# 4_POWER_48_TO_12.net
KiCad netlist of a schematic drawn in Altium Designer
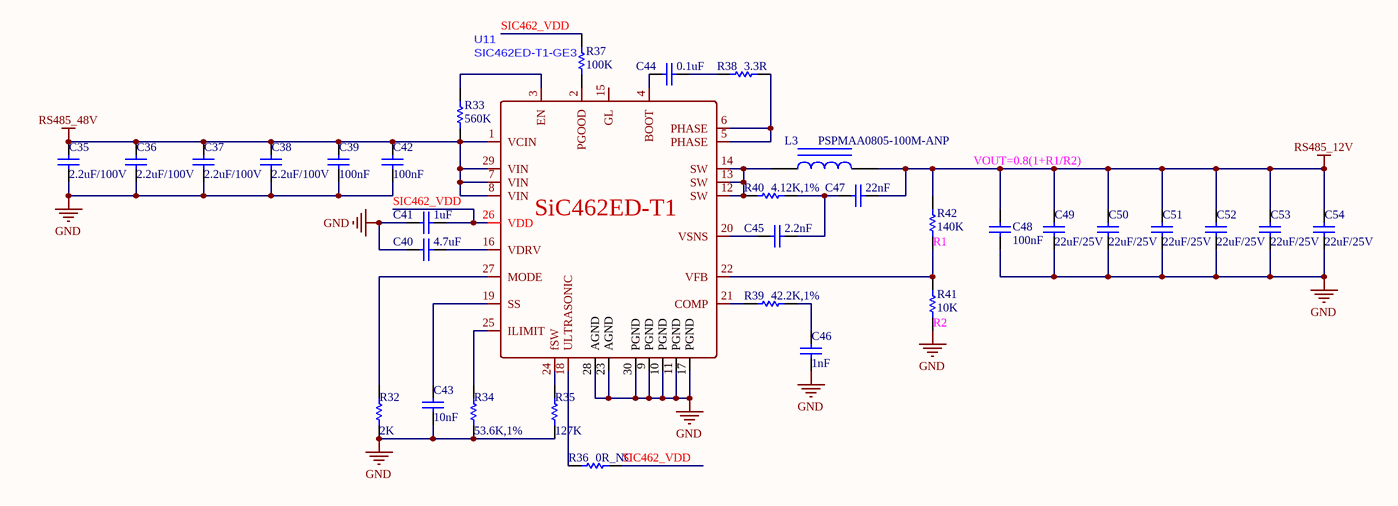
[diagram p0: 4.POWER_48_TO_12.SchDoc]

(export (version "E")
  (design (tool "Eeschema 10.0.6"))
  (components
    (comp (ref "C35")
      (value "2.2uF/100V")
      (footprint "1206C")
      (description "Capacitor")
      (fields (field (name "PARTNUMBER") "CAP100NF") (field (name "PUBLISHER") "Altium Limited"))
      (libsource (lib "Miscellaneous Devices") (part "Cap"))
    )
    (comp (ref "C36")
      (value "2.2uF/100V")
      (footprint "1206C")
      (description "Capacitor")
      (fields (field (name "PARTNUMBER") "CAP100NF") (field (name "PUBLISHER") "Altium Limited"))
      (libsource (lib "Miscellaneous Devices") (part "Cap"))
    )
    (comp (ref "C37")
      (value "2.2uF/100V")
      (footprint "1206C")
      (description "Capacitor")
      (fields (field (name "PARTNUMBER") "CAP100NF") (field (name "PUBLISHER") "Altium Limited"))
      (libsource (lib "Miscellaneous Devices") (part "Cap"))
    )
    (comp (ref "C38")
      (value "2.2uF/100V")
      (footprint "1206C")
      (description "Capacitor")
      (fields (field (name "PARTNUMBER") "CAP100NF") (field (name "PUBLISHER") "Altium Limited"))
      (libsource (lib "Miscellaneous Devices") (part "Cap"))
    )
    (comp (ref "C39")
      (value "100nF")
      (footprint "0402")
      (description "Capacitor")
      (fields (field (name "PARTNUMBER") "CAP100NF") (field (name "PUBLISHER") "Altium Limited"))
      (libsource (lib "Miscellaneous Devices") (part "Cap"))
    )
    (comp (ref "C40")
      (value "4.7uF")
      (footprint "0402")
      (description "Capacitor")
      (fields (field (name "PARTNUMBER") "CAP100NF") (field (name "PUBLISHER") "Altium Limited"))
      (libsource (lib "Miscellaneous Devices") (part "Cap"))
    )
    (comp (ref "C41")
      (value "1uF")
      (footprint "0402")
      (description "Capacitor")
      (fields (field (name "PARTNUMBER") "CAP100NF") (field (name "PUBLISHER") "Altium Limited"))
      (libsource (lib "Miscellaneous Devices") (part "Cap"))
    )
    (comp (ref "C42")
      (value "100nF")
      (footprint "0402")
      (description "Capacitor")
      (fields (field (name "PARTNUMBER") "CAP100NF") (field (name "PUBLISHER") "Altium Limited"))
      (libsource (lib "Miscellaneous Devices") (part "Cap"))
    )
    (comp (ref "C43")
      (value "10nF")
      (footprint "0402")
      (description "Capacitor")
      (fields (field (name "PARTNUMBER") "CAP100NF") (field (name "PUBLISHER") "Altium Limited"))
      (libsource (lib "Miscellaneous Devices") (part "Cap"))
    )
    (comp (ref "C44")
      (value "0.1uF")
      (footprint "0402")
      (description "Capacitor")
      (fields (field (name "PARTNUMBER") "CAP100NF") (field (name "PUBLISHER") "Altium Limited"))
      (libsource (lib "Miscellaneous Devices") (part "Cap"))
    )
    (comp (ref "C45")
      (value "2.2nF")
      (footprint "0402")
      (description "Capacitor")
      (fields (field (name "PARTNUMBER") "CAP100NF") (field (name "PUBLISHER") "Altium Limited"))
      (libsource (lib "Miscellaneous Devices") (part "Cap"))
    )
    (comp (ref "C46")
      (value "1nF")
      (footprint "0402")
      (description "Capacitor")
      (fields (field (name "PARTNUMBER") "CAP100NF") (field (name "PUBLISHER") "Altium Limited"))
      (libsource (lib "Miscellaneous Devices") (part "Cap"))
    )
    (comp (ref "C47")
      (value "22nF")
      (footprint "0402")
      (description "Capacitor")
      (fields (field (name "PARTNUMBER") "CAP100NF") (field (name "PUBLISHER") "Altium Limited"))
      (libsource (lib "Miscellaneous Devices") (part "Cap"))
    )
    (comp (ref "C48")
      (value "100nF")
      (footprint "0402")
      (description "Capacitor")
      (fields (field (name "PARTNUMBER") "CAP100NF") (field (name "PUBLISHER") "Altium Limited"))
      (libsource (lib "Miscellaneous Devices") (part "Cap"))
    )
    (comp (ref "C49")
      (value "22uF/25V")
      (footprint "0805C")
      (description "Capacitor")
      (fields (field (name "PARTNUMBER") "CAP100NF") (field (name "PUBLISHER") "Altium Limited"))
      (libsource (lib "Miscellaneous Devices") (part "Cap"))
    )
    (comp (ref "C50")
      (value "22uF/25V")
      (footprint "0805C")
      (description "Capacitor")
      (fields (field (name "PARTNUMBER") "CAP100NF") (field (name "PUBLISHER") "Altium Limited"))
      (libsource (lib "Miscellaneous Devices") (part "Cap"))
    )
    (comp (ref "C51")
      (value "22uF/25V")
      (footprint "0805C")
      (description "Capacitor")
      (fields (field (name "PARTNUMBER") "CAP100NF") (field (name "PUBLISHER") "Altium Limited"))
      (libsource (lib "Miscellaneous Devices") (part "Cap"))
    )
    (comp (ref "C52")
      (value "22uF/25V")
      (footprint "0805C")
      (description "Capacitor")
      (fields (field (name "PARTNUMBER") "CAP100NF") (field (name "PUBLISHER") "Altium Limited"))
      (libsource (lib "Miscellaneous Devices") (part "Cap"))
    )
    (comp (ref "C53")
      (value "22uF/25V")
      (footprint "0805C")
      (description "Capacitor")
      (fields (field (name "PARTNUMBER") "CAP100NF") (field (name "PUBLISHER") "Altium Limited"))
      (libsource (lib "Miscellaneous Devices") (part "Cap"))
    )
    (comp (ref "C54")
      (value "22uF/25V")
      (footprint "0805C")
      (description "Capacitor")
      (fields (field (name "PARTNUMBER") "CAP100NF") (field (name "PUBLISHER") "Altium Limited"))
      (libsource (lib "Miscellaneous Devices") (part "Cap"))
    )
    (comp (ref "L3")
      (value "PSPMAA0805-100M-ANP")
      (footprint "IND-SMD_L8.5-W8.0_PCC-M0854M")
      (description "贴片电感")
      (libsource (lib "Miscellaneous Devices LC") (part "0603 3.9nH 0.3nH"))
    )
    (comp (ref "R32")
      (value "2K")
      (footprint "0402")
      (description "Resistor")
      (fields (field (name "PARTNUMBER") "RES22R") (field (name "PUBLISHER") "Altium Limited"))
      (libsource (lib "Miscellaneous Devices") (part "Res1"))
    )
    (comp (ref "R33")
      (value "560K")
      (footprint "0402")
      (description "Resistor")
      (fields (field (name "PARTNUMBER") "RES22R") (field (name "PUBLISHER") "Altium Limited"))
      (libsource (lib "Miscellaneous Devices") (part "Res1"))
    )
    (comp (ref "R34")
      (value "53.6K,1%")
      (footprint "0402")
      (description "Resistor")
      (fields (field (name "PARTNUMBER") "RES22R") (field (name "PUBLISHER") "Altium Limited"))
      (libsource (lib "Miscellaneous Devices") (part "Res1"))
    )
    (comp (ref "R35")
      (value "127K")
      (footprint "0402")
      (description "Resistor")
      (fields (field (name "PARTNUMBER") "RES22R") (field (name "PUBLISHER") "Altium Limited"))
      (libsource (lib "Miscellaneous Devices") (part "Res1"))
    )
    (comp (ref "R36")
      (value "0R_NC")
      (footprint "0402")
      (description "Resistor")
      (fields (field (name "PARTNUMBER") "RES22R") (field (name "PUBLISHER") "Altium Limited"))
      (libsource (lib "Miscellaneous Devices") (part "Res1"))
    )
    (comp (ref "R37")
      (value "100K")
      (footprint "0402")
      (description "Resistor")
      (fields (field (name "PARTNUMBER") "RES22R") (field (name "PUBLISHER") "Altium Limited"))
      (libsource (lib "Miscellaneous Devices") (part "Res1"))
    )
    (comp (ref "R38")
      (value "3.3R")
      (footprint "0402")
      (description "Resistor")
      (fields (field (name "PARTNUMBER") "RES22R") (field (name "PUBLISHER") "Altium Limited"))
      (libsource (lib "Miscellaneous Devices") (part "Res1"))
    )
    (comp (ref "R39")
      (value "42.2K,1%")
      (footprint "0402")
      (description "Resistor")
      (fields (field (name "PARTNUMBER") "RES22R") (field (name "PUBLISHER") "Altium Limited"))
      (libsource (lib "Miscellaneous Devices") (part "Res1"))
    )
    (comp (ref "R40")
      (value "4.12K,1%")
      (footprint "0402")
      (description "Resistor")
      (fields (field (name "PARTNUMBER") "RES22R") (field (name "PUBLISHER") "Altium Limited"))
      (libsource (lib "Miscellaneous Devices") (part "Res1"))
    )
    (comp (ref "R41")
      (value "10K")
      (footprint "0402")
      (description "Resistor")
      (fields (field (name "PARTNUMBER") "RES22R") (field (name "PUBLISHER") "Altium Limited"))
      (libsource (lib "Miscellaneous Devices") (part "Res1"))
    )
    (comp (ref "R42")
      (value "140K")
      (footprint "0402")
      (description "Resistor")
      (fields (field (name "PARTNUMBER") "RES22R") (field (name "PUBLISHER") "Altium Limited"))
      (libsource (lib "Miscellaneous Devices") (part "Res1"))
    )
    (comp (ref "U11")
      (value "SIC462ED-T1-GE3")
      (footprint "MLP55-27_L5.0-W5.0-P0.50-TL_SIC46XXX")
      (libsource (lib "HM2") (part "SIC462ED-T1-GE3"))
    )
  )
  (nets
    (net (code "1") (name "/SIC462_VDD") (class "Default")
      (node (ref "C41") (pin "1") (pinfunction "1_1") (pintype "passive"))
      (node (ref "R36") (pin "1") (pinfunction "1_1") (pintype "passive"))
      (node (ref "R37") (pin "2") (pinfunction "2_2") (pintype "passive"))
      (node (ref "U11") (pin "26") (pinfunction "VDD_26") (pintype "passive"))
    )
    (net (code "2") (name "GND") (class "Default")
      (node (ref "C35") (pin "2") (pinfunction "2_2") (pintype "passive"))
      (node (ref "C36") (pin "2") (pinfunction "2_2") (pintype "passive"))
      (node (ref "C37") (pin "2") (pinfunction "2_2") (pintype "passive"))
      (node (ref "C38") (pin "2") (pinfunction "2_2") (pintype "passive"))
      (node (ref "C39") (pin "2") (pinfunction "2_2") (pintype "passive"))
      (node (ref "C40") (pin "2") (pinfunction "2_2") (pintype "passive"))
      (node (ref "C41") (pin "2") (pinfunction "2_2") (pintype "passive"))
      (node (ref "C42") (pin "2") (pinfunction "2_2") (pintype "passive"))
      (node (ref "C43") (pin "1") (pinfunction "1_1") (pintype "passive"))
      (node (ref "C46") (pin "1") (pinfunction "1_1") (pintype "passive"))
      (node (ref "C48") (pin "2") (pinfunction "2_2") (pintype "passive"))
      (node (ref "C49") (pin "2") (pinfunction "2_2") (pintype "passive"))
      (node (ref "C50") (pin "2") (pinfunction "2_2") (pintype "passive"))
      (node (ref "C51") (pin "2") (pinfunction "2_2") (pintype "passive"))
      (node (ref "C52") (pin "2") (pinfunction "2_2") (pintype "passive"))
      (node (ref "C53") (pin "2") (pinfunction "2_2") (pintype "passive"))
      (node (ref "C54") (pin "2") (pinfunction "2_2") (pintype "passive"))
      (node (ref "R32") (pin "2") (pinfunction "2_2") (pintype "passive"))
      (node (ref "R34") (pin "2") (pinfunction "2_2") (pintype "passive"))
      (node (ref "R35") (pin "2") (pinfunction "2_2") (pintype "passive"))
      (node (ref "R41") (pin "1") (pinfunction "1_1") (pintype "passive"))
      (node (ref "U11") (pin "10") (pinfunction "PGND_10") (pintype "passive"))
      (node (ref "U11") (pin "11") (pinfunction "PGND_11") (pintype "passive"))
      (node (ref "U11") (pin "17") (pinfunction "PGND_17") (pintype "passive"))
      (node (ref "U11") (pin "23") (pinfunction "AGND_23") (pintype "passive"))
      (node (ref "U11") (pin "28") (pinfunction "AGND_28") (pintype "passive"))
      (node (ref "U11") (pin "30") (pinfunction "PGND_30") (pintype "passive"))
      (node (ref "U11") (pin "9") (pinfunction "PGND_9") (pintype "passive"))
    )
    (net (code "3") (name "Net-(C44-Pad1)") (class "Default")
      (node (ref "C44") (pin "1") (pinfunction "1_1") (pintype "passive"))
      (node (ref "R38") (pin "1") (pinfunction "1_1") (pintype "passive"))
    )
    (net (code "4") (name "Net-(C45-Pad1)") (class "Default")
      (node (ref "C45") (pin "1") (pinfunction "1_1") (pintype "passive"))
      (node (ref "C47") (pin "1") (pinfunction "1_1") (pintype "passive"))
      (node (ref "R40") (pin "2") (pinfunction "2_2") (pintype "passive"))
    )
    (net (code "5") (name "Net-(C46-Pad2)") (class "Default")
      (node (ref "C46") (pin "2") (pinfunction "2_2") (pintype "passive"))
      (node (ref "R39") (pin "2") (pinfunction "2_2") (pintype "passive"))
    )
    (net (code "6") (name "Net-(L3-Pad1)") (class "Default")
      (node (ref "L3") (pin "1") (pinfunction "1_1") (pintype "passive"))
      (node (ref "R40") (pin "1") (pinfunction "1_1") (pintype "passive"))
      (node (ref "U11") (pin "12") (pinfunction "SW_12") (pintype "passive"))
      (node (ref "U11") (pin "13") (pinfunction "SW_13") (pintype "passive"))
      (node (ref "U11") (pin "14") (pinfunction "SW_14") (pintype "passive"))
    )
    (net (code "7") (name "Net-(R38-Pad2)") (class "Default")
      (node (ref "R38") (pin "2") (pinfunction "2_2") (pintype "passive"))
      (node (ref "U11") (pin "5") (pinfunction "PHASE_5") (pintype "passive"))
      (node (ref "U11") (pin "6") (pinfunction "PHASE_6") (pintype "passive"))
    )
    (net (code "8") (name "Net-(U11-BOOT)") (class "Default")
      (node (ref "C44") (pin "2") (pinfunction "2_2") (pintype "passive"))
      (node (ref "U11") (pin "4") (pinfunction "BOOT_4") (pintype "passive"))
    )
    (net (code "9") (name "Net-(U11-COMP)") (class "Default")
      (node (ref "R39") (pin "1") (pinfunction "1_1") (pintype "passive"))
      (node (ref "U11") (pin "21") (pinfunction "COMP_21") (pintype "passive"))
    )
    (net (code "10") (name "Net-(U11-EN)") (class "Default")
      (node (ref "R33") (pin "2") (pinfunction "2_2") (pintype "passive"))
      (node (ref "U11") (pin "3") (pinfunction "EN_3") (pintype "passive"))
    )
    (net (code "11") (name "Net-(U11-ILIMIT)") (class "Default")
      (node (ref "R34") (pin "1") (pinfunction "1_1") (pintype "passive"))
      (node (ref "U11") (pin "25") (pinfunction "ILIMIT_25") (pintype "passive"))
    )
    (net (code "12") (name "Net-(U11-MODE)") (class "Default")
      (node (ref "R32") (pin "1") (pinfunction "1_1") (pintype "passive"))
      (node (ref "U11") (pin "27") (pinfunction "MODE_27") (pintype "passive"))
    )
    (net (code "13") (name "Net-(U11-PGOOD)") (class "Default")
      (node (ref "R37") (pin "1") (pinfunction "1_1") (pintype "passive"))
      (node (ref "U11") (pin "2") (pinfunction "PGOOD_2") (pintype "passive"))
    )
    (net (code "14") (name "Net-(U11-SS)") (class "Default")
      (node (ref "C43") (pin "2") (pinfunction "2_2") (pintype "passive"))
      (node (ref "U11") (pin "19") (pinfunction "SS_19") (pintype "passive"))
    )
    (net (code "15") (name "Net-(U11-ULTRASONIC)") (class "Default")
      (node (ref "R36") (pin "2") (pinfunction "2_2") (pintype "passive"))
      (node (ref "U11") (pin "18") (pinfunction "ULTRASONIC_18") (pintype "passive"))
    )
    (net (code "16") (name "Net-(U11-VDRV)") (class "Default")
      (node (ref "C40") (pin "1") (pinfunction "1_1") (pintype "passive"))
      (node (ref "U11") (pin "16") (pinfunction "VDRV_16") (pintype "passive"))
    )
    (net (code "17") (name "Net-(U11-VFB)") (class "Default")
      (node (ref "R41") (pin "2") (pinfunction "2_2") (pintype "passive"))
      (node (ref "R42") (pin "1") (pinfunction "1_1") (pintype "passive"))
      (node (ref "U11") (pin "22") (pinfunction "VFB_22") (pintype "passive"))
    )
    (net (code "18") (name "Net-(U11-VSNS)") (class "Default")
      (node (ref "C45") (pin "2") (pinfunction "2_2") (pintype "passive"))
      (node (ref "U11") (pin "20") (pinfunction "VSNS_20") (pintype "passive"))
    )
    (net (code "19") (name "Net-(U11-fSW)") (class "Default")
      (node (ref "R35") (pin "1") (pinfunction "1_1") (pintype "passive"))
      (node (ref "U11") (pin "24") (pinfunction "fSW_24") (pintype "passive"))
    )
    (net (code "20") (name "RS485_12V") (class "Default")
      (node (ref "C47") (pin "2") (pinfunction "2_2") (pintype "passive"))
      (node (ref "C48") (pin "1") (pinfunction "1_1") (pintype "passive"))
      (node (ref "C49") (pin "1") (pinfunction "1_1") (pintype "passive"))
      (node (ref "C50") (pin "1") (pinfunction "1_1") (pintype "passive"))
      (node (ref "C51") (pin "1") (pinfunction "1_1") (pintype "passive"))
      (node (ref "C52") (pin "1") (pinfunction "1_1") (pintype "passive"))
      (node (ref "C53") (pin "1") (pinfunction "1_1") (pintype "passive"))
      (node (ref "C54") (pin "1") (pinfunction "1_1") (pintype "passive"))
      (node (ref "L3") (pin "2") (pinfunction "2_2") (pintype "passive"))
      (node (ref "R42") (pin "2") (pinfunction "2_2") (pintype "passive"))
    )
    (net (code "21") (name "RS485_48V") (class "Default")
      (node (ref "C35") (pin "1") (pinfunction "1_1") (pintype "passive"))
      (node (ref "C36") (pin "1") (pinfunction "1_1") (pintype "passive"))
      (node (ref "C37") (pin "1") (pinfunction "1_1") (pintype "passive"))
      (node (ref "C38") (pin "1") (pinfunction "1_1") (pintype "passive"))
      (node (ref "C39") (pin "1") (pinfunction "1_1") (pintype "passive"))
      (node (ref "C42") (pin "1") (pinfunction "1_1") (pintype "passive"))
      (node (ref "R33") (pin "1") (pinfunction "1_1") (pintype "passive"))
      (node (ref "U11") (pin "1") (pinfunction "VCIN_1") (pintype "passive"))
      (node (ref "U11") (pin "29") (pinfunction "VIN_29") (pintype "passive"))
      (node (ref "U11") (pin "7") (pinfunction "VIN_7") (pintype "passive"))
      (node (ref "U11") (pin "8") (pinfunction "VIN_8") (pintype "passive"))
    )
    (net (code "22") (name "unconnected-(U11-GL-Pad15)") (class "Default")
      (node (ref "U11") (pin "15") (pinfunction "GL_15") (pintype "passive"))
    )
  )
)
